# Schematics.net
KiCad netlist of a schematic drawn in EAGLE
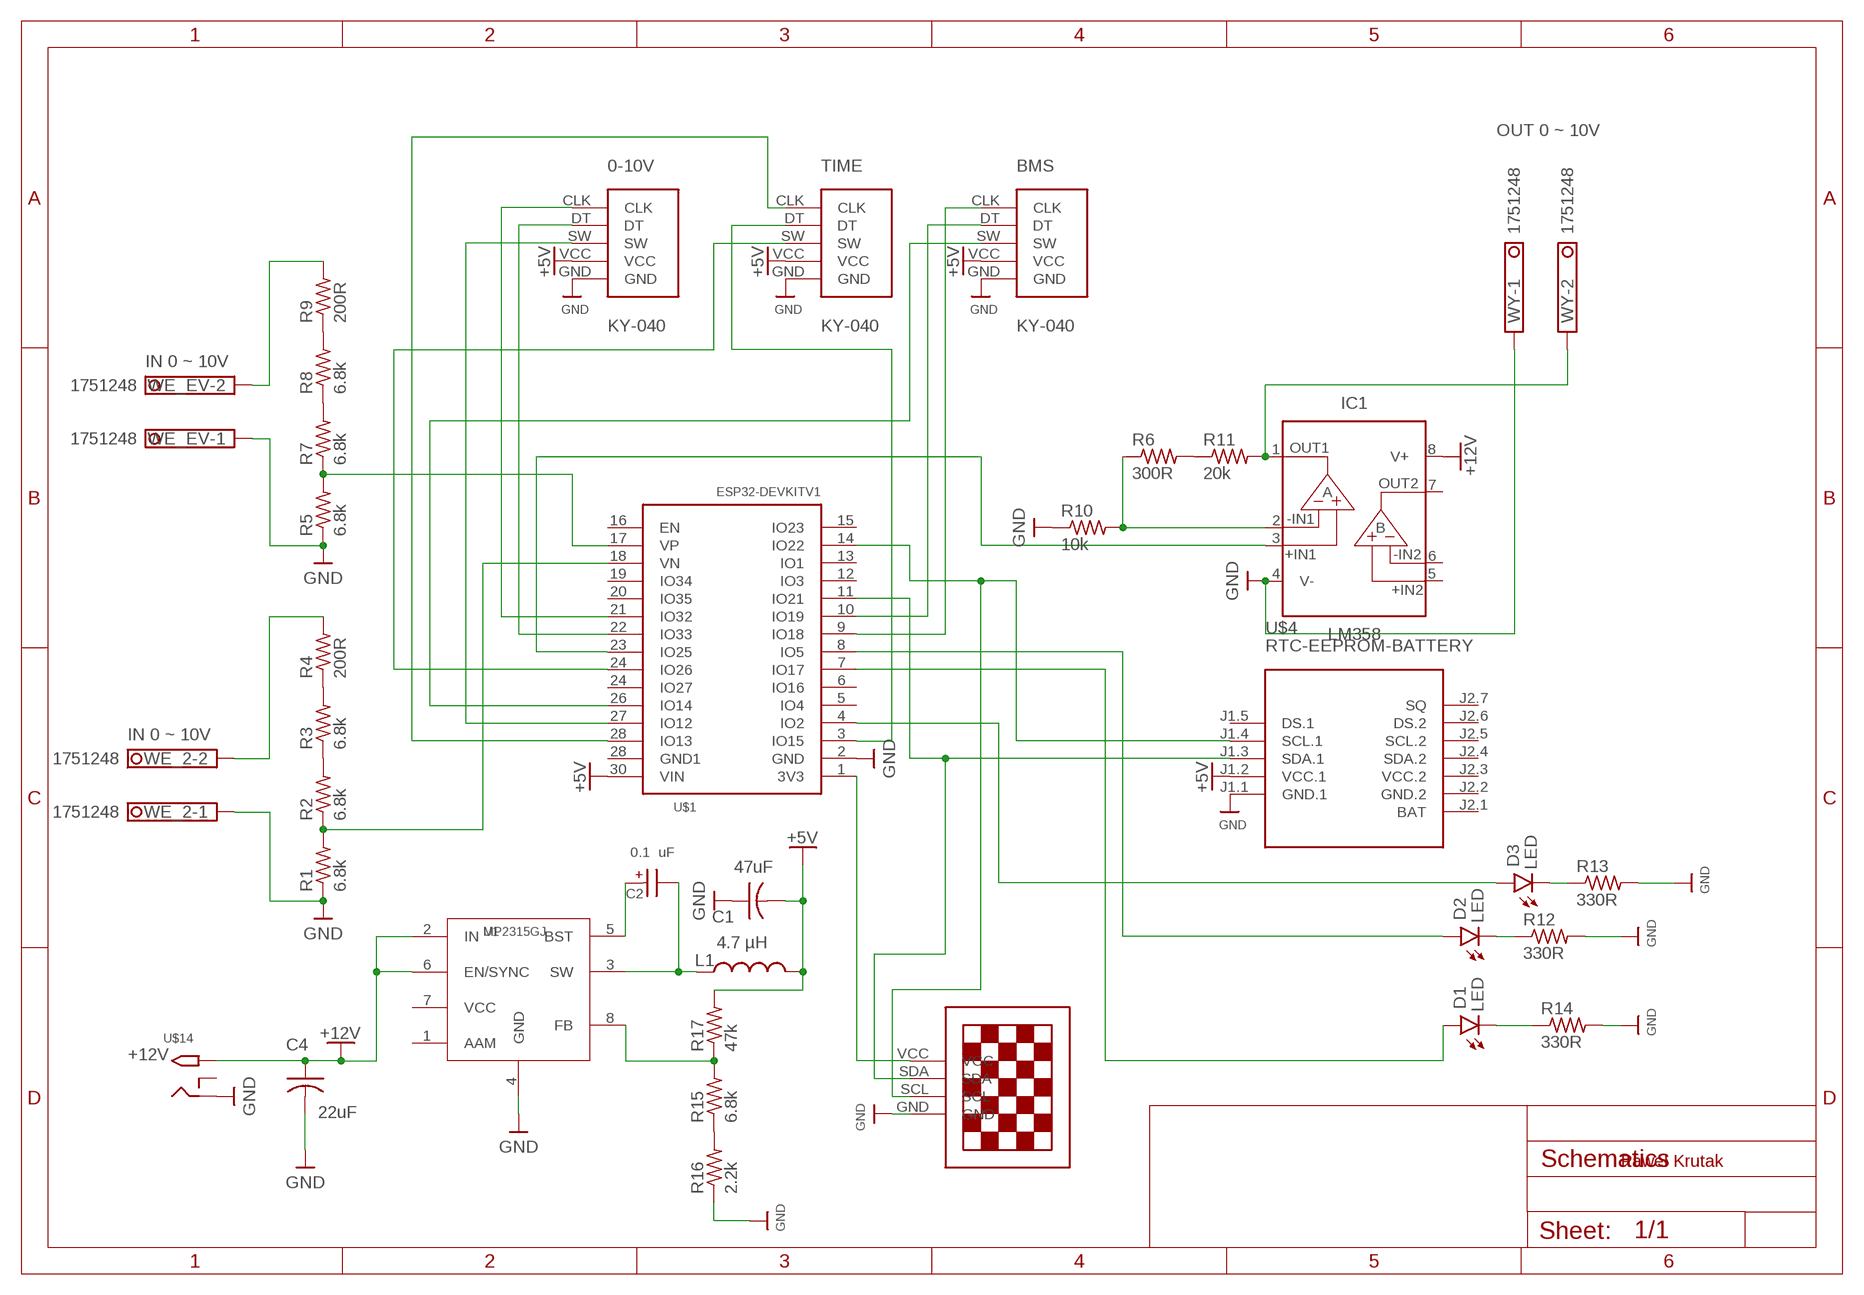
[diagram p0: schematic, sheet 1]

(export (version "E")
  (design (tool "Eeschema 10.0.6"))
  (components
    (comp (ref "0-10V")
      (value "KY-040")
      (footprint "eagle-import:KY-040-PORT")
      (fields (field (name "MF") "Joy-IT"))
      (libsource (lib "eagle-import") (part "KY-040"))
    )
    (comp (ref "BMS")
      (value "KY-040")
      (footprint "eagle-import:KY-040-PORT")
      (fields (field (name "MF") "Joy-IT"))
      (libsource (lib "eagle-import") (part "KY-040"))
    )
    (comp (ref "C1")
      (value "47uF")
      (footprint "eagle-import:CAP_RADIAL_2MM")
      (fields
        (field (name "DIGIKEY_PART_NUMBER") "P5179-ND")
        (field (name "MANUFACTURER") "Panasonic Electronic Components")
        (field (name "MPN") "ECA-1HM220")
        (field (name "CREATED_BY") "PCBLayout.com")
      )
      (libsource (lib "eagle-import") (part "ECA-1HM220"))
    )
    (comp (ref "C2")
      (value "0.1 uF")
      (footprint "eagle-import:WCAP-ATG5_5X11(DXL)")
      (libsource (lib "eagle-import") (part "WCAP-ATG5_5X11_860020772001"))
    )
    (comp (ref "C4")
      (value "22uF")
      (footprint "eagle-import:CAP_RADIAL_2MM")
      (fields
        (field (name "DIGIKEY_PART_NUMBER") "P5179-ND")
        (field (name "MANUFACTURER") "Panasonic Electronic Components")
        (field (name "MPN") "ECA-1HM220")
        (field (name "CREATED_BY") "PCBLayout.com")
      )
      (libsource (lib "eagle-import") (part "ECA-1HM220"))
    )
    (comp (ref "D1")
      (value "LED")
      (footprint "eagle-import:LEDRD254W60D565H860B_W90")
      (libsource (lib "eagle-import") (part "LEDWHITE90"))
    )
    (comp (ref "D2")
      (value "LED")
      (footprint "eagle-import:LEDRD254W60D565H860B_W90")
      (libsource (lib "eagle-import") (part "LEDWHITE90"))
    )
    (comp (ref "D3")
      (value "LED")
      (footprint "eagle-import:LEDRD254W60D565H860B_W90")
      (libsource (lib "eagle-import") (part "LEDWHITE90"))
    )
    (comp (ref "IC1")
      (value "LM358")
      (footprint "eagle-import:DIP826W53P254L959H508Q8B")
      (fields (field (name "MANUFACTURER") "Generic"))
      (libsource (lib "eagle-import") (part "LM358_DIP"))
    )
    (comp (ref "L1")
      (value "4.7 µH")
      (footprint "eagle-import:SRN6045")
      (libsource (lib "eagle-import") (part "INDUCTORSRN6045"))
    )
    (comp (ref "R1")
      (value "6.8k")
      (footprint "eagle-import:M0805")
      (libsource (lib "eagle-import") (part "R-US_M0805"))
    )
    (comp (ref "R2")
      (value "6.8k")
      (footprint "eagle-import:M0805")
      (libsource (lib "eagle-import") (part "R-US_M0805"))
    )
    (comp (ref "R3")
      (value "6.8k")
      (footprint "eagle-import:M0805")
      (libsource (lib "eagle-import") (part "R-US_M0805"))
    )
    (comp (ref "R4")
      (value "200R")
      (footprint "eagle-import:M0805")
      (libsource (lib "eagle-import") (part "R-US_M0805"))
    )
    (comp (ref "R5")
      (value "6.8k")
      (footprint "eagle-import:M0805")
      (libsource (lib "eagle-import") (part "R-US_M0805"))
    )
    (comp (ref "R6")
      (value "300R")
      (footprint "eagle-import:M0805")
      (libsource (lib "eagle-import") (part "R-US_M0805"))
    )
    (comp (ref "R7")
      (value "6.8k")
      (footprint "eagle-import:M0805")
      (libsource (lib "eagle-import") (part "R-US_M0805"))
    )
    (comp (ref "R8")
      (value "6.8k")
      (footprint "eagle-import:M0805")
      (libsource (lib "eagle-import") (part "R-US_M0805"))
    )
    (comp (ref "R9")
      (value "200R")
      (footprint "eagle-import:M0805")
      (libsource (lib "eagle-import") (part "R-US_M0805"))
    )
    (comp (ref "R10")
      (value "10k")
      (footprint "eagle-import:M0805")
      (libsource (lib "eagle-import") (part "R-US_M0805"))
    )
    (comp (ref "R11")
      (value "20k")
      (footprint "eagle-import:M0805")
      (libsource (lib "eagle-import") (part "R-US_M0805"))
    )
    (comp (ref "R12")
      (value "330R")
      (footprint "eagle-import:M0805")
      (libsource (lib "eagle-import") (part "R-US_M0805"))
    )
    (comp (ref "R13")
      (value "330R")
      (footprint "eagle-import:M0805")
      (libsource (lib "eagle-import") (part "R-US_M0805"))
    )
    (comp (ref "R14")
      (value "330R")
      (footprint "eagle-import:M0805")
      (libsource (lib "eagle-import") (part "R-US_M0805"))
    )
    (comp (ref "R15")
      (value "6.8k")
      (footprint "eagle-import:M0805")
      (libsource (lib "eagle-import") (part "R-US_M0805"))
    )
    (comp (ref "R16")
      (value "2.2k")
      (footprint "eagle-import:M0805")
      (libsource (lib "eagle-import") (part "R-US_M0805"))
    )
    (comp (ref "R17")
      (value "47k")
      (footprint "eagle-import:M0805")
      (libsource (lib "eagle-import") (part "R-US_M0805"))
    )
    (comp (ref "TIME")
      (value "KY-040")
      (footprint "eagle-import:KY-040-PORT")
      (fields (field (name "MF") "Joy-IT"))
      (libsource (lib "eagle-import") (part "KY-040"))
    )
    (comp (ref "U$1")
      (value "ESP32DEVKITV1")
      (footprint "eagle-import:ESP32-DEVKITV1")
      (libsource (lib "eagle-import") (part "ESP32DEVKITV1"))
    )
    (comp (ref "U$4")
      (value "RTC-EEPROM-BATTERY")
      (footprint "eagle-import:RTC_EEPROM_BATTERY")
      (libsource (lib "eagle-import") (part "RTC-EEPROM-BATTERY"))
    )
    (comp (ref "U$8")
      (value "13\"OLED13\"OLED")
      (footprint "eagle-import:1.3_OLED")
      (libsource (lib "eagle-import") (part "13{dblquote}OLED13{dblquote}OLED"))
    )
    (comp (ref "U$14")
      (value "2.1MMJACKTHM")
      (footprint "eagle-import:PJ-102A")
      (libsource (lib "eagle-import") (part "2.1MMJACKTHM"))
    )
    (comp (ref "U1")
      (value "MP2315GJ")
      (footprint "eagle-import:SOT-23-8")
      (fields (field (name "MPN") "MP2315"))
      (libsource (lib "eagle-import") (part "MP2315GJ"))
    )
    (comp (ref "WE_2")
      (value "1751248")
      (footprint "eagle-import:1751248")
      (libsource (lib "eagle-import") (part "1751248"))
    )
    (comp (ref "WE_EV")
      (value "1751248")
      (footprint "eagle-import:1751248")
      (libsource (lib "eagle-import") (part "1751248"))
    )
    (comp (ref "WY")
      (value "1751248")
      (footprint "eagle-import:1751248")
      (libsource (lib "eagle-import") (part "1751248"))
    )
  )
  (nets
    (net (code "1") (name "+5V") (class "Default")
      (node (ref "0-10V") (pin "VCC") (pinfunction "VCC_VCC") (pintype "power_in"))
      (node (ref "BMS") (pin "VCC") (pinfunction "VCC_VCC") (pintype "power_in"))
      (node (ref "C1") (pin "2") (pinfunction "2_2") (pintype "passive"))
      (node (ref "L1") (pin "2") (pinfunction "2_2") (pintype "passive"))
      (node (ref "R17") (pin "2") (pinfunction "2_2") (pintype "passive"))
      (node (ref "TIME") (pin "VCC") (pinfunction "VCC_VCC") (pintype "power_in"))
      (node (ref "U$1") (pin "30") (pinfunction "VIN_30") (pintype "bidirectional"))
      (node (ref "U$4") (pin "J1.2") (pinfunction "VCC.1_J1.2") (pintype "power_in"))
    )
    (net (code "2") (name "+12V") (class "Default")
      (node (ref "C4") (pin "1") (pinfunction "1_1") (pintype "passive"))
      (node (ref "IC1") (pin "8") (pinfunction "V+_8") (pintype "bidirectional"))
      (node (ref "U$14") (pin "TIP") (pinfunction "TIP_TIP") (pintype "bidirectional"))
      (node (ref "U1") (pin "2") (pinfunction "IN_2") (pintype "bidirectional"))
      (node (ref "U1") (pin "6") (pinfunction "EN/SYNC_6") (pintype "bidirectional"))
    )
    (net (code "3") (name "/GND.2") (class "Default")
      (node (ref "U$4") (pin "J2.2") (pinfunction "GND.2_J2.2") (pintype "power_in"))
    )
    (net (code "4") (name "/VCC.2") (class "Default")
      (node (ref "U$4") (pin "J2.3") (pinfunction "VCC.2_J2.3") (pintype "power_in"))
    )
    (net (code "5") (name "GND") (class "Default")
      (node (ref "0-10V") (pin "GND") (pinfunction "GND_GND") (pintype "power_in"))
      (node (ref "BMS") (pin "GND") (pinfunction "GND_GND") (pintype "power_in"))
      (node (ref "C1") (pin "1") (pinfunction "1_1") (pintype "passive"))
      (node (ref "C4") (pin "2") (pinfunction "2_2") (pintype "passive"))
      (node (ref "IC1") (pin "4") (pinfunction "V-_4") (pintype "bidirectional"))
      (node (ref "R1") (pin "1") (pinfunction "1_1") (pintype "passive"))
      (node (ref "R10") (pin "1") (pinfunction "1_1") (pintype "passive"))
      (node (ref "R12") (pin "2") (pinfunction "2_2") (pintype "passive"))
      (node (ref "R13") (pin "2") (pinfunction "2_2") (pintype "passive"))
      (node (ref "R14") (pin "2") (pinfunction "2_2") (pintype "passive"))
      (node (ref "R16") (pin "1") (pinfunction "1_1") (pintype "passive"))
      (node (ref "R5") (pin "1") (pinfunction "1_1") (pintype "passive"))
      (node (ref "TIME") (pin "GND") (pinfunction "GND_GND") (pintype "power_in"))
      (node (ref "U$1") (pin "2") (pinfunction "GND_2") (pintype "bidirectional"))
      (node (ref "U$14") (pin "RING") (pinfunction "RING_RING") (pintype "bidirectional"))
      (node (ref "U$4") (pin "J1.1") (pinfunction "GND.1_J1.1") (pintype "power_in"))
      (node (ref "U$8") (pin "GND") (pinfunction "GND_GND") (pintype "bidirectional"))
      (node (ref "U1") (pin "4") (pinfunction "GND_4") (pintype "bidirectional"))
      (node (ref "WE_2") (pin "1") (pinfunction "K_1") (pintype "passive"))
      (node (ref "WE_EV") (pin "1") (pinfunction "K_1") (pintype "passive"))
      (node (ref "WY") (pin "1") (pinfunction "K_1") (pintype "passive"))
    )
    (net (code "6") (name "Net-(C2-+)") (class "Default")
      (node (ref "C2") (pin "1") (pinfunction "+_1") (pintype "passive"))
      (node (ref "U1") (pin "5") (pinfunction "BST_5") (pintype "bidirectional"))
    )
    (net (code "7") (name "Net-(C2--)") (class "Default")
      (node (ref "C2") (pin "2") (pinfunction "-_2") (pintype "passive"))
      (node (ref "L1") (pin "1") (pinfunction "1_1") (pintype "passive"))
      (node (ref "U1") (pin "3") (pinfunction "SW_3") (pintype "bidirectional"))
    )
    (net (code "8") (name "Net-(D1-A)") (class "Default")
      (node (ref "D1") (pin "1") (pinfunction "A_1") (pintype "passive"))
      (node (ref "U$1") (pin "7") (pinfunction "IO17_7") (pintype "bidirectional"))
    )
    (net (code "9") (name "Net-(D1-C)") (class "Default")
      (node (ref "D1") (pin "2") (pinfunction "C_2") (pintype "passive"))
      (node (ref "R14") (pin "1") (pinfunction "1_1") (pintype "passive"))
    )
    (net (code "10") (name "Net-(D2-A)") (class "Default")
      (node (ref "D2") (pin "1") (pinfunction "A_1") (pintype "passive"))
      (node (ref "U$1") (pin "8") (pinfunction "IO5_8") (pintype "bidirectional"))
    )
    (net (code "11") (name "Net-(D2-C)") (class "Default")
      (node (ref "D2") (pin "2") (pinfunction "C_2") (pintype "passive"))
      (node (ref "R12") (pin "1") (pinfunction "1_1") (pintype "passive"))
    )
    (net (code "12") (name "Net-(D3-A)") (class "Default")
      (node (ref "D3") (pin "1") (pinfunction "A_1") (pintype "passive"))
      (node (ref "U$1") (pin "4") (pinfunction "IO2_4") (pintype "bidirectional"))
    )
    (net (code "13") (name "Net-(D3-C)") (class "Default")
      (node (ref "D3") (pin "2") (pinfunction "C_2") (pintype "passive"))
      (node (ref "R13") (pin "1") (pinfunction "1_1") (pintype "passive"))
    )
    (net (code "14") (name "Net-(IC1-+IN1)") (class "Default")
      (node (ref "IC1") (pin "3") (pinfunction "+IN1_3") (pintype "input"))
      (node (ref "U$1") (pin "23") (pinfunction "IO25_23") (pintype "bidirectional"))
    )
    (net (code "15") (name "Net-(IC1--IN1)") (class "Default")
      (node (ref "IC1") (pin "2") (pinfunction "-IN1_2") (pintype "input"))
      (node (ref "R10") (pin "2") (pinfunction "2_2") (pintype "passive"))
      (node (ref "R6") (pin "1") (pinfunction "1_1") (pintype "passive"))
    )
    (net (code "16") (name "Net-(IC1-OUT1)") (class "Default")
      (node (ref "IC1") (pin "1") (pinfunction "OUT1_1") (pintype "passive"))
      (node (ref "R11") (pin "2") (pinfunction "2_2") (pintype "passive"))
      (node (ref "WY") (pin "2") (pinfunction "K_2") (pintype "passive"))
    )
    (net (code "17") (name "Net-(R2-Pad2)") (class "Default")
      (node (ref "R2") (pin "2") (pinfunction "2_2") (pintype "passive"))
      (node (ref "R3") (pin "1") (pinfunction "1_1") (pintype "passive"))
    )
    (net (code "18") (name "Net-(R3-Pad2)") (class "Default")
      (node (ref "R3") (pin "2") (pinfunction "2_2") (pintype "passive"))
      (node (ref "R4") (pin "1") (pinfunction "1_1") (pintype "passive"))
    )
    (net (code "19") (name "Net-(R7-Pad2)") (class "Default")
      (node (ref "R7") (pin "2") (pinfunction "2_2") (pintype "passive"))
      (node (ref "R8") (pin "1") (pinfunction "1_1") (pintype "passive"))
    )
    (net (code "20") (name "Net-(R8-Pad2)") (class "Default")
      (node (ref "R8") (pin "2") (pinfunction "2_2") (pintype "passive"))
      (node (ref "R9") (pin "1") (pinfunction "1_1") (pintype "passive"))
    )
    (net (code "21") (name "Net-(R11-Pad1)") (class "Default")
      (node (ref "R11") (pin "1") (pinfunction "1_1") (pintype "passive"))
      (node (ref "R6") (pin "2") (pinfunction "2_2") (pintype "passive"))
    )
    (net (code "22") (name "Net-(R15-Pad1)") (class "Default")
      (node (ref "R15") (pin "1") (pinfunction "1_1") (pintype "passive"))
      (node (ref "R16") (pin "2") (pinfunction "2_2") (pintype "passive"))
    )
    (net (code "23") (name "Net-(U$1-3V3)") (class "Default")
      (node (ref "U$1") (pin "1") (pinfunction "3V3_1") (pintype "bidirectional"))
      (node (ref "U$8") (pin "VCC") (pinfunction "VCC_VCC") (pintype "bidirectional"))
    )
    (net (code "24") (name "Net-(U$1-IO12)") (class "Default")
      (node (ref "0-10V") (pin "SW") (pinfunction "SW_SW") (pintype "output"))
      (node (ref "U$1") (pin "27") (pinfunction "IO12_27") (pintype "bidirectional"))
    )
    (net (code "25") (name "Net-(U$1-IO13)") (class "Default")
      (node (ref "TIME") (pin "CLK") (pinfunction "CLK_CLK") (pintype "output"))
      (node (ref "U$1") (pin "28") (pinfunction "IO13_28") (pintype "bidirectional"))
    )
    (net (code "26") (name "Net-(U$1-IO14)") (class "Default")
      (node (ref "BMS") (pin "SW") (pinfunction "SW_SW") (pintype "output"))
      (node (ref "U$1") (pin "26") (pinfunction "IO14_26") (pintype "bidirectional"))
    )
    (net (code "27") (name "Net-(U$1-IO15)") (class "Default")
      (node (ref "TIME") (pin "DT") (pinfunction "DT_DT") (pintype "output"))
      (node (ref "U$1") (pin "3") (pinfunction "IO15_3") (pintype "bidirectional"))
    )
    (net (code "28") (name "Net-(U$1-IO18)") (class "Default")
      (node (ref "BMS") (pin "CLK") (pinfunction "CLK_CLK") (pintype "output"))
      (node (ref "U$1") (pin "9") (pinfunction "IO18_9") (pintype "bidirectional"))
    )
    (net (code "29") (name "Net-(U$1-IO19)") (class "Default")
      (node (ref "BMS") (pin "DT") (pinfunction "DT_DT") (pintype "output"))
      (node (ref "U$1") (pin "10") (pinfunction "IO19_10") (pintype "bidirectional"))
    )
    (net (code "30") (name "Net-(U$1-IO21)") (class "Default")
      (node (ref "U$1") (pin "11") (pinfunction "IO21_11") (pintype "bidirectional"))
      (node (ref "U$4") (pin "J1.3") (pinfunction "SDA.1_J1.3") (pintype "bidirectional"))
      (node (ref "U$8") (pin "SDA") (pinfunction "SDA_SDA") (pintype "bidirectional"))
    )
    (net (code "31") (name "Net-(U$1-IO22)") (class "Default")
      (node (ref "U$1") (pin "14") (pinfunction "IO22_14") (pintype "bidirectional"))
      (node (ref "U$4") (pin "J1.4") (pinfunction "SCL.1_J1.4") (pintype "bidirectional"))
      (node (ref "U$8") (pin "SCL") (pinfunction "SCL_SCL") (pintype "bidirectional"))
    )
    (net (code "32") (name "Net-(U$1-IO26)") (class "Default")
      (node (ref "TIME") (pin "SW") (pinfunction "SW_SW") (pintype "output"))
      (node (ref "U$1") (pin "24") (pinfunction "IO26_24") (pintype "bidirectional"))
    )
    (net (code "33") (name "Net-(U$1-IO32)") (class "Default")
      (node (ref "0-10V") (pin "CLK") (pinfunction "CLK_CLK") (pintype "output"))
      (node (ref "U$1") (pin "21") (pinfunction "IO32_21") (pintype "bidirectional"))
    )
    (net (code "34") (name "Net-(U$1-IO33)") (class "Default")
      (node (ref "0-10V") (pin "DT") (pinfunction "DT_DT") (pintype "output"))
      (node (ref "U$1") (pin "22") (pinfunction "IO33_22") (pintype "bidirectional"))
    )
    (net (code "35") (name "Net-(U$1-VN)") (class "Default")
      (node (ref "R1") (pin "2") (pinfunction "2_2") (pintype "passive"))
      (node (ref "R2") (pin "1") (pinfunction "1_1") (pintype "passive"))
      (node (ref "U$1") (pin "18") (pinfunction "VN_18") (pintype "bidirectional"))
    )
    (net (code "36") (name "Net-(U$1-VP)") (class "Default")
      (node (ref "R5") (pin "2") (pinfunction "2_2") (pintype "passive"))
      (node (ref "R7") (pin "1") (pinfunction "1_1") (pintype "passive"))
      (node (ref "U$1") (pin "17") (pinfunction "VP_17") (pintype "bidirectional"))
    )
    (net (code "37") (name "Net-(U1-FB)") (class "Default")
      (node (ref "R15") (pin "2") (pinfunction "2_2") (pintype "passive"))
      (node (ref "R17") (pin "1") (pinfunction "1_1") (pintype "passive"))
      (node (ref "U1") (pin "8") (pinfunction "FB_8") (pintype "bidirectional"))
    )
    (net (code "38") (name "Net-(WE_2B-K)") (class "Default")
      (node (ref "R4") (pin "2") (pinfunction "2_2") (pintype "passive"))
      (node (ref "WE_2") (pin "2") (pinfunction "K_2") (pintype "passive"))
    )
    (net (code "39") (name "Net-(WE_EVB-K)") (class "Default")
      (node (ref "R9") (pin "2") (pinfunction "2_2") (pintype "passive"))
      (node (ref "WE_EV") (pin "2") (pinfunction "K_2") (pintype "passive"))
    )
    (net (code "40") (name "unconnected-(IC1-+IN2-Pad5)") (class "Default")
      (node (ref "IC1") (pin "5") (pinfunction "+IN2_5") (pintype "passive"))
    )
    (net (code "41") (name "unconnected-(IC1--IN2-Pad6)") (class "Default")
      (node (ref "IC1") (pin "6") (pinfunction "-IN2_6") (pintype "passive"))
    )
    (net (code "42") (name "unconnected-(IC1-OUT2-Pad7)") (class "Default")
      (node (ref "IC1") (pin "7") (pinfunction "OUT2_7") (pintype "passive"))
    )
    (net (code "43") (name "unconnected-(U$1-EN-Pad16)") (class "Default")
      (node (ref "U$1") (pin "16") (pinfunction "EN_16") (pintype "bidirectional"))
    )
    (net (code "44") (name "unconnected-(U$1-GND1-Pad28)") (class "Default")
      (node (ref "U$1") (pin "28") (pinfunction "GND1_28") (pintype "bidirectional"))
    )
    (net (code "45") (name "unconnected-(U$1-IO1-Pad13)") (class "Default")
      (node (ref "U$1") (pin "13") (pinfunction "IO1_13") (pintype "bidirectional"))
    )
    (net (code "46") (name "unconnected-(U$1-IO3-Pad12)") (class "Default")
      (node (ref "U$1") (pin "12") (pinfunction "IO3_12") (pintype "bidirectional"))
    )
    (net (code "47") (name "unconnected-(U$1-IO4-Pad5)") (class "Default")
      (node (ref "U$1") (pin "5") (pinfunction "IO4_5") (pintype "bidirectional"))
    )
    (net (code "48") (name "unconnected-(U$1-IO16-Pad6)") (class "Default")
      (node (ref "U$1") (pin "6") (pinfunction "IO16_6") (pintype "bidirectional"))
    )
    (net (code "49") (name "unconnected-(U$1-IO23-Pad15)") (class "Default")
      (node (ref "U$1") (pin "15") (pinfunction "IO23_15") (pintype "bidirectional"))
    )
    (net (code "50") (name "unconnected-(U$1-IO27-Pad24)") (class "Default")
      (node (ref "U$1") (pin "24") (pinfunction "IO27_24") (pintype "bidirectional"))
    )
    (net (code "51") (name "unconnected-(U$1-IO34-Pad19)") (class "Default")
      (node (ref "U$1") (pin "19") (pinfunction "IO34_19") (pintype "bidirectional"))
    )
    (net (code "52") (name "unconnected-(U$1-IO35-Pad20)") (class "Default")
      (node (ref "U$1") (pin "20") (pinfunction "IO35_20") (pintype "bidirectional"))
    )
    (net (code "53") (name "unconnected-(U$4-BAT-PadJ2.1)") (class "Default")
      (node (ref "U$4") (pin "J2.1") (pinfunction "BAT_J2.1") (pintype "bidirectional"))
    )
    (net (code "54") (name "unconnected-(U$4-DS.1-PadJ1.5)") (class "Default")
      (node (ref "U$4") (pin "J1.5") (pinfunction "DS.1_J1.5") (pintype "bidirectional"))
    )
    (net (code "55") (name "unconnected-(U$4-DS.2-PadJ2.6)") (class "Default")
      (node (ref "U$4") (pin "J2.6") (pinfunction "DS.2_J2.6") (pintype "bidirectional"))
    )
    (net (code "56") (name "unconnected-(U$4-SCL.2-PadJ2.5)") (class "Default")
      (node (ref "U$4") (pin "J2.5") (pinfunction "SCL.2_J2.5") (pintype "bidirectional"))
    )
    (net (code "57") (name "unconnected-(U$4-SDA.2-PadJ2.4)") (class "Default")
      (node (ref "U$4") (pin "J2.4") (pinfunction "SDA.2_J2.4") (pintype "bidirectional"))
    )
    (net (code "58") (name "unconnected-(U$4-SQ-PadJ2.7)") (class "Default")
      (node (ref "U$4") (pin "J2.7") (pinfunction "SQ_J2.7") (pintype "bidirectional"))
    )
    (net (code "59") (name "unconnected-(U$14-PadRING_SW)") (class "Default")
      (node (ref "U$14") (pin "RING_SW") (pinfunction "RING_SW_RING_SW") (pintype "bidirectional"))
    )
    (net (code "60") (name "unconnected-(U1-AAM-Pad1)") (class "Default")
      (node (ref "U1") (pin "1") (pinfunction "AAM_1") (pintype "bidirectional"))
    )
    (net (code "61") (name "unconnected-(U1-VCC-Pad7)") (class "Default")
      (node (ref "U1") (pin "7") (pinfunction "VCC_7") (pintype "bidirectional"))
    )
  )
)
